# MB_audio_esp.net
KiCad netlist of a schematic drawn in Altium Designer
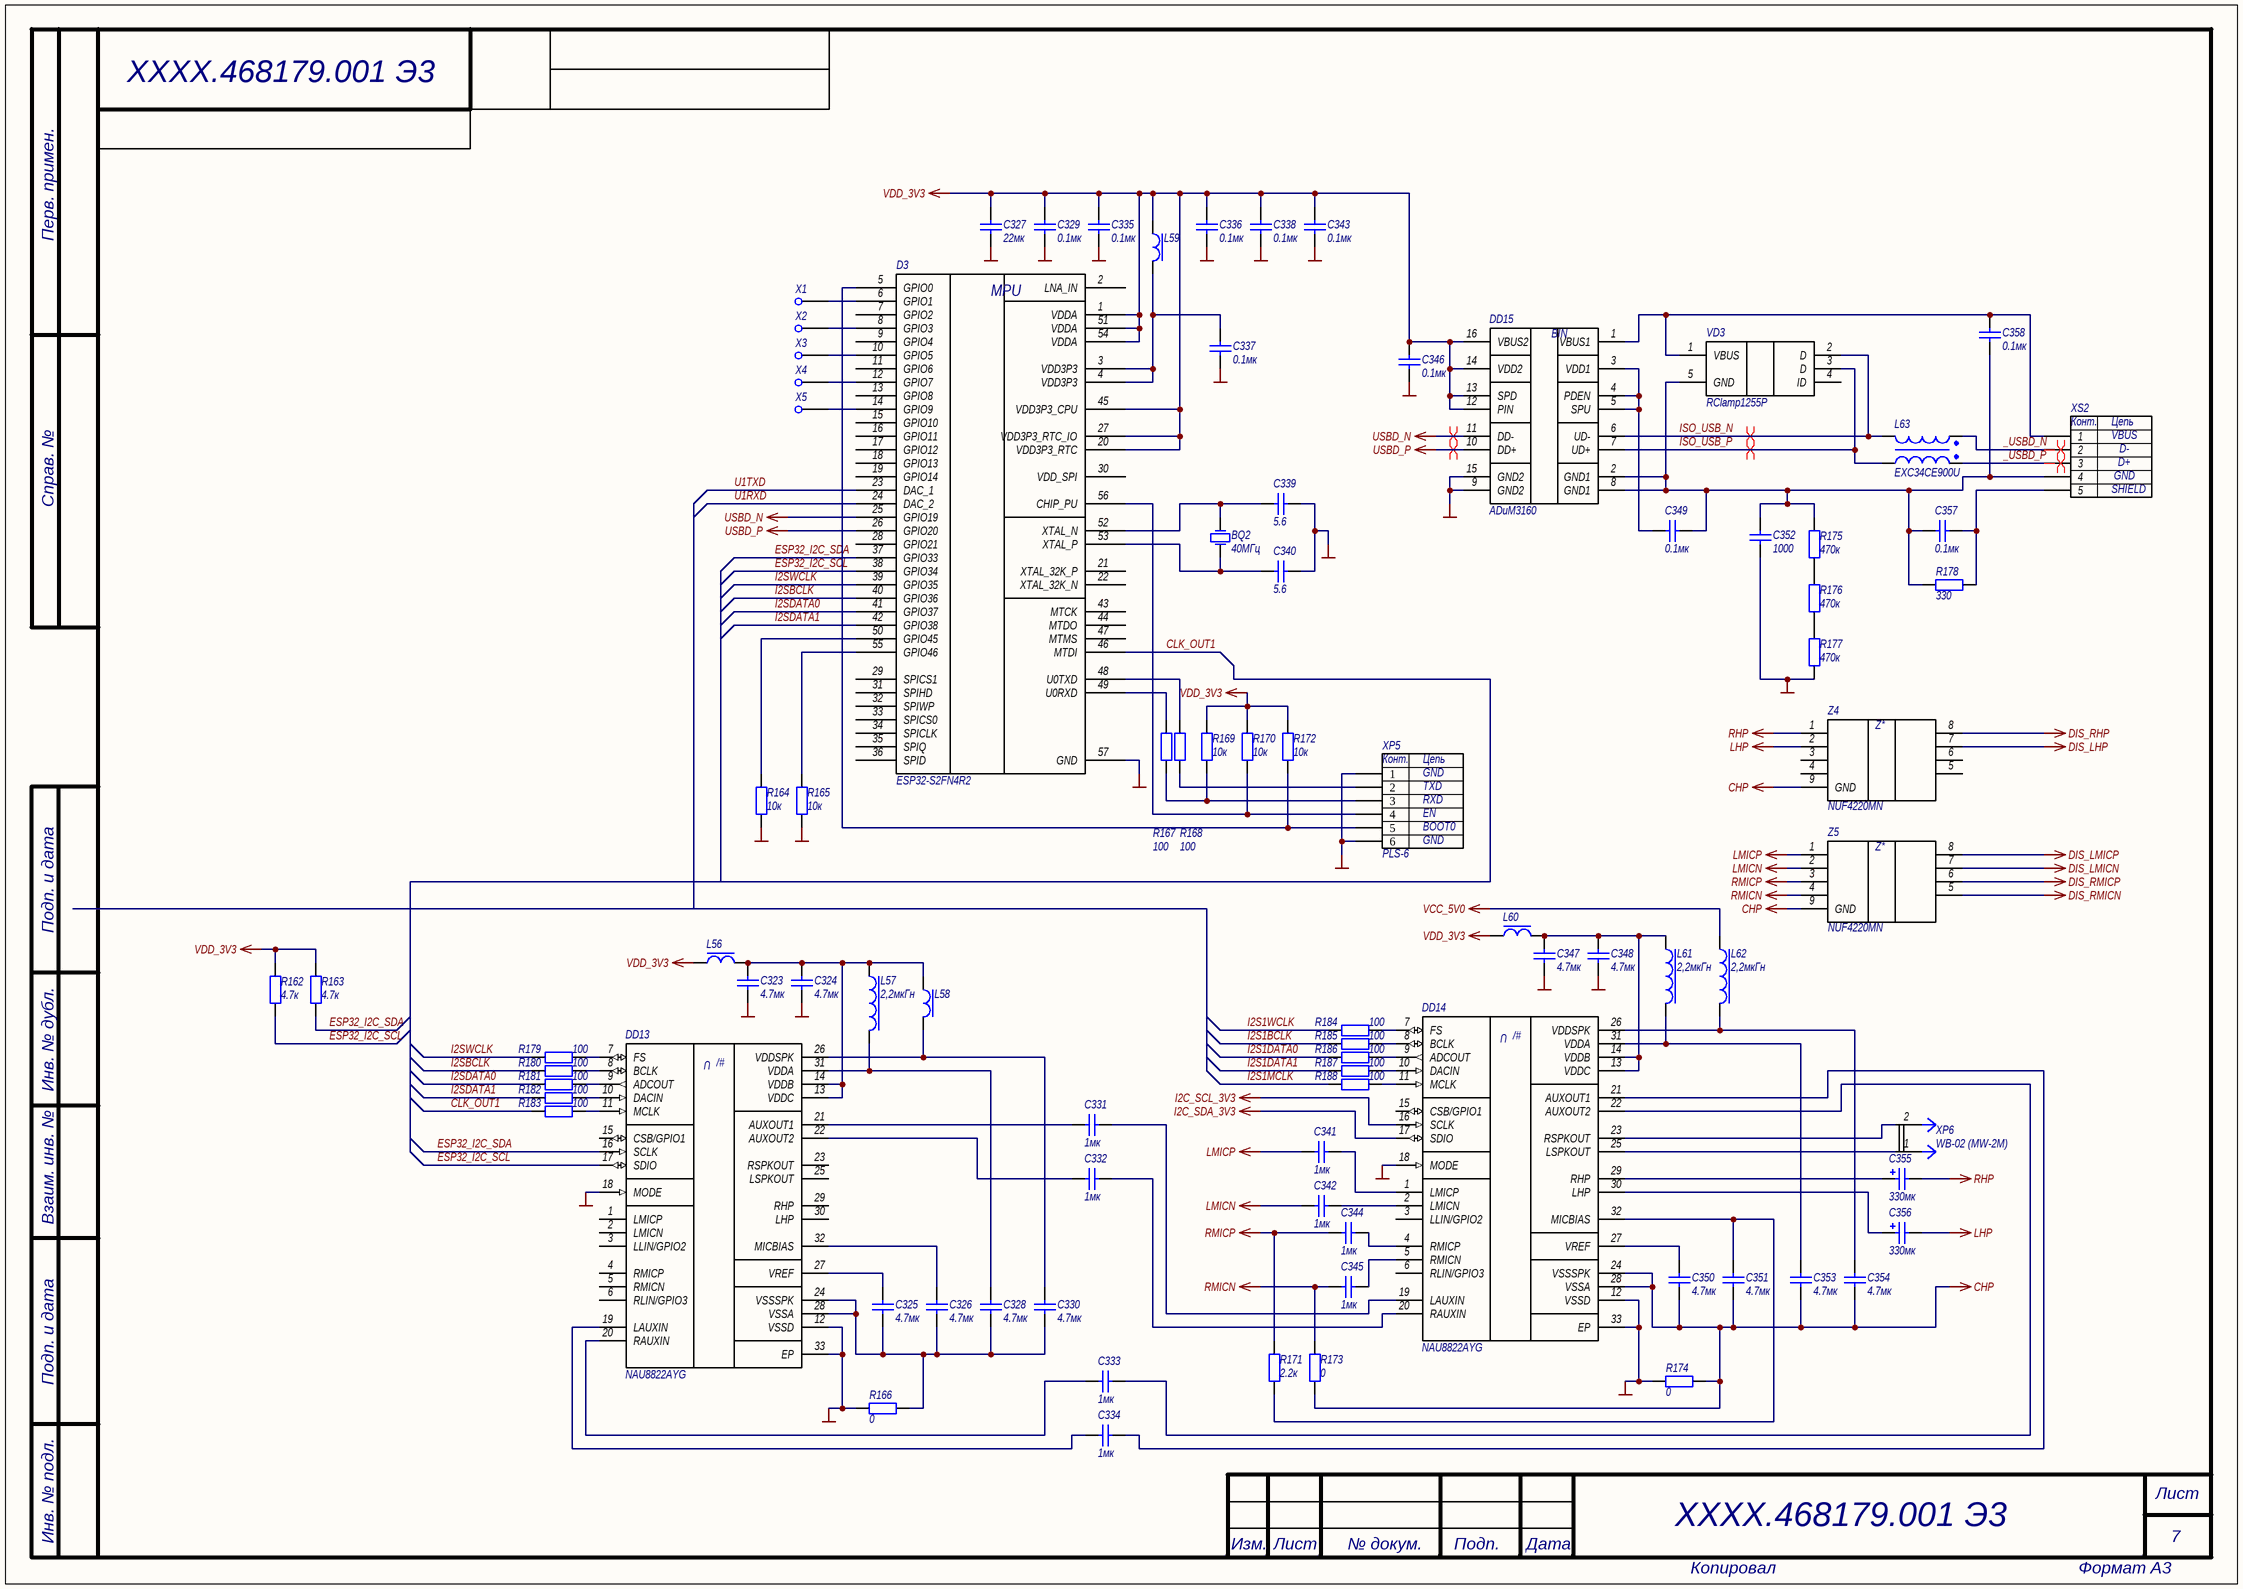
[diagram p0: MB_audio_esp.SchDoc]

(export (version "E")
  (design (tool "Eeschema 10.0.6"))
  (components
    (comp (ref "BQ2")
      (value "40МГц")
      (footprint "ABRACOM ABM10")
      (description "Резонатор кварцевый")
      (fields (field (name "TOLERANCE") "±50 ppm") (field (name "MANUFACTURER") "ABRACON"))
      (libsource (lib "nels_other") (part "Кварц ABM10AIG-40.000MHZ"))
    )
    (comp (ref "C323")
      (value "4.7мк")
      (footprint "CAPC2012X12L")
      (description "Кер. ЧИП-конденсатор")
      (fields (field (name "TOLERANCE") "±20%") (field (name "MANUFACTURER") "Murata"))
      (libsource (lib "nels_caps") (part "Кер.ЧИП конд. 0805 4,7мкФ X5R 20% 16В"))
    )
    (comp (ref "C324")
      (value "4.7мк")
      (footprint "CAPC2012X12L")
      (description "Кер. ЧИП-конденсатор")
      (fields (field (name "TOLERANCE") "±20%") (field (name "MANUFACTURER") "Murata"))
      (libsource (lib "nels_caps") (part "Кер.ЧИП конд. 0805 4,7мкФ X5R 20% 16В"))
    )
    (comp (ref "C325")
      (value "4.7мк")
      (footprint "CAPC2012X12L")
      (description "Кер. ЧИП-конденсатор")
      (fields (field (name "TOLERANCE") "±20%") (field (name "MANUFACTURER") "Murata"))
      (libsource (lib "nels_caps") (part "Кер.ЧИП конд. 0805 4,7мкФ X5R 20% 16В"))
    )
    (comp (ref "C326")
      (value "4.7мк")
      (footprint "CAPC2012X12L")
      (description "Кер. ЧИП-конденсатор")
      (fields (field (name "TOLERANCE") "±20%") (field (name "MANUFACTURER") "Murata"))
      (libsource (lib "nels_caps") (part "Кер.ЧИП конд. 0805 4,7мкФ X5R 20% 16В"))
    )
    (comp (ref "C327")
      (value "22мк")
      (footprint "CAPC2012X12L")
      (description "Кер. ЧИП-конденсатор")
      (fields (field (name "MANUFACTURER") "TDK") (field (name "TOLERANCE") "±10%"))
      (libsource (lib "nels_caps") (part "Кер.ЧИП конд. 0805 22мкФ X5R 10% 16В"))
    )
    (comp (ref "C328")
      (value "4.7мк")
      (footprint "CAPC2012X12L")
      (description "Кер. ЧИП-конденсатор")
      (fields (field (name "TOLERANCE") "±20%") (field (name "MANUFACTURER") "Murata"))
      (libsource (lib "nels_caps") (part "Кер.ЧИП конд. 0805 4,7мкФ X5R 20% 16В"))
    )
    (comp (ref "C329")
      (value "0.1мк")
      (footprint "CAPC1005X06N")
      (description "Кер. ЧИП-конденсатор")
      (fields (field (name "TOLERANCE") "±10%"))
      (libsource (lib "nels") (part "Кер.ЧИП конд. 0402 0.1мкФ X7R 10%, 16В"))
    )
    (comp (ref "C330")
      (value "4.7мк")
      (footprint "CAPC2012X12L")
      (description "Кер. ЧИП-конденсатор")
      (fields (field (name "TOLERANCE") "±20%") (field (name "MANUFACTURER") "Murata"))
      (libsource (lib "nels_caps") (part "Кер.ЧИП конд. 0805 4,7мкФ X5R 20% 16В"))
    )
    (comp (ref "C331")
      (value "1мк")
      (footprint "CAPC1005X06N")
      (description "Кер. ЧИП-конденсатор")
      (fields (field (name "TOLERANCE") "±10%"))
      (libsource (lib "nels_caps") (part "Кер.ЧИП конд. 0402 1мкФ X5R 10%, 10В"))
    )
    (comp (ref "C332")
      (value "1мк")
      (footprint "CAPC1005X06N")
      (description "Кер. ЧИП-конденсатор")
      (fields (field (name "TOLERANCE") "±10%"))
      (libsource (lib "nels_caps") (part "Кер.ЧИП конд. 0402 1мкФ X5R 10%, 10В"))
    )
    (comp (ref "C333")
      (value "1мк")
      (footprint "CAPC1005X06N")
      (description "Кер. ЧИП-конденсатор")
      (fields (field (name "TOLERANCE") "±10%"))
      (libsource (lib "nels_caps") (part "Кер.ЧИП конд. 0402 1мкФ X5R 10%, 10В"))
    )
    (comp (ref "C334")
      (value "1мк")
      (footprint "CAPC1005X06N")
      (description "Кер. ЧИП-конденсатор")
      (fields (field (name "TOLERANCE") "±10%"))
      (libsource (lib "nels_caps") (part "Кер.ЧИП конд. 0402 1мкФ X5R 10%, 10В"))
    )
    (comp (ref "C335")
      (value "0.1мк")
      (footprint "CAPC1005X06N")
      (description "Кер. ЧИП-конденсатор")
      (fields (field (name "TOLERANCE") "±10%"))
      (libsource (lib "nels") (part "Кер.ЧИП конд. 0402 0.1мкФ X7R 10%, 16В"))
    )
    (comp (ref "C336")
      (value "0.1мк")
      (footprint "CAPC1005X06N")
      (description "Кер. ЧИП-конденсатор")
      (fields (field (name "TOLERANCE") "±10%"))
      (libsource (lib "nels") (part "Кер.ЧИП конд. 0402 0.1мкФ X7R 10%, 16В"))
    )
    (comp (ref "C337")
      (value "0.1мк")
      (footprint "CAPC1005X06N")
      (description "Кер. ЧИП-конденсатор")
      (fields (field (name "TOLERANCE") "±10%"))
      (libsource (lib "nels") (part "Кер.ЧИП конд. 0402 0.1мкФ X7R 10%, 16В"))
    )
    (comp (ref "C338")
      (value "0.1мк")
      (footprint "CAPC1005X06N")
      (description "Кер. ЧИП-конденсатор")
      (fields (field (name "TOLERANCE") "±10%"))
      (libsource (lib "nels") (part "Кер.ЧИП конд. 0402 0.1мкФ X7R 10%, 16В"))
    )
    (comp (ref "C339")
      (value "5.6")
      (footprint "CAPC1005X06N")
      (description "Кер. ЧИП-конденсатор")
      (fields (field (name "TOLERANCE") "±5%"))
      (libsource (lib "nels_caps") (part "Кер.ЧИП конд. 0402 5.6пФ C0G, 50В"))
    )
    (comp (ref "C340")
      (value "5.6")
      (footprint "CAPC1005X06N")
      (description "Кер. ЧИП-конденсатор")
      (fields (field (name "TOLERANCE") "±5%"))
      (libsource (lib "nels_caps") (part "Кер.ЧИП конд. 0402 5.6пФ C0G, 50В"))
    )
    (comp (ref "C341")
      (value "1мк")
      (footprint "CAPC1005X06N")
      (description "Кер. ЧИП-конденсатор")
      (fields (field (name "TOLERANCE") "±10%"))
      (libsource (lib "nels_caps") (part "Кер.ЧИП конд. 0402 1мкФ X5R 10%, 10В"))
    )
    (comp (ref "C342")
      (value "1мк")
      (footprint "CAPC1005X06N")
      (description "Кер. ЧИП-конденсатор")
      (fields (field (name "TOLERANCE") "±10%"))
      (libsource (lib "nels_caps") (part "Кер.ЧИП конд. 0402 1мкФ X5R 10%, 10В"))
    )
    (comp (ref "C343")
      (value "0.1мк")
      (footprint "CAPC1005X06N")
      (description "Кер. ЧИП-конденсатор")
      (fields (field (name "TOLERANCE") "±10%"))
      (libsource (lib "nels") (part "Кер.ЧИП конд. 0402 0.1мкФ X7R 10%, 16В"))
    )
    (comp (ref "C344")
      (value "1мк")
      (footprint "CAPC1005X06N")
      (description "Кер. ЧИП-конденсатор")
      (fields (field (name "TOLERANCE") "±10%"))
      (libsource (lib "nels_caps") (part "Кер.ЧИП конд. 0402 1мкФ X5R 10%, 10В"))
    )
    (comp (ref "C345")
      (value "1мк")
      (footprint "CAPC1005X06N")
      (description "Кер. ЧИП-конденсатор")
      (fields (field (name "TOLERANCE") "±10%"))
      (libsource (lib "nels_caps") (part "Кер.ЧИП конд. 0402 1мкФ X5R 10%, 10В"))
    )
    (comp (ref "C346")
      (value "0.1мк")
      (footprint "CAPC1005X06N")
      (description "Кер. ЧИП-конденсатор")
      (fields (field (name "TOLERANCE") "±10%"))
      (libsource (lib "nels") (part "Кер.ЧИП конд. 0402 0.1мкФ X7R 10%, 16В"))
    )
    (comp (ref "C347")
      (value "4.7мк")
      (footprint "CAPC2012X12L")
      (description "Кер. ЧИП-конденсатор")
      (fields (field (name "TOLERANCE") "±20%") (field (name "MANUFACTURER") "Murata"))
      (libsource (lib "nels_caps") (part "Кер.ЧИП конд. 0805 4,7мкФ X5R 20% 16В"))
    )
    (comp (ref "C348")
      (value "4.7мк")
      (footprint "CAPC2012X12L")
      (description "Кер. ЧИП-конденсатор")
      (fields (field (name "TOLERANCE") "±20%") (field (name "MANUFACTURER") "Murata"))
      (libsource (lib "nels_caps") (part "Кер.ЧИП конд. 0805 4,7мкФ X5R 20% 16В"))
    )
    (comp (ref "C349")
      (value "0.1мк")
      (footprint "CAPC1608X08L")
      (description "Кер. ЧИП-конденсатор")
      (fields (field (name "TOLERANCE") "±10%") (field (name "MANUFACTURER") "Murata"))
      (libsource (lib "nels_caps") (part "Кер.ЧИП конд. 0603 0.1мкФ X7R 10% 50В"))
    )
    (comp (ref "C350")
      (value "4.7мк")
      (footprint "CAPC2012X12L")
      (description "Кер. ЧИП-конденсатор")
      (fields (field (name "TOLERANCE") "±20%") (field (name "MANUFACTURER") "Murata"))
      (libsource (lib "nels_caps") (part "Кер.ЧИП конд. 0805 4,7мкФ X5R 20% 16В"))
    )
    (comp (ref "C351")
      (value "4.7мк")
      (footprint "CAPC2012X12L")
      (description "Кер. ЧИП-конденсатор")
      (fields (field (name "TOLERANCE") "±20%") (field (name "MANUFACTURER") "Murata"))
      (libsource (lib "nels_caps") (part "Кер.ЧИП конд. 0805 4,7мкФ X5R 20% 16В"))
    )
    (comp (ref "C352")
      (value "1000")
      (footprint "CAPRD7.5-9x5")
      (description "Защищенные конденсаторы 1000pF 250Vrms 20% L/S=10mm Bulk long")
      (fields
        (field (name "MANUFACTURER") "MURATA")
        (field (name "TOLERANCE") "±10%")
        (field (name "PUBLISHER") "Altium Limited")
      )
      (libsource (lib "nels_caps") (part "Конденсатор керамический защищенный 1000pF 250V AC (DE1E3KX102MA4BN01F)"))
    )
    (comp (ref "C353")
      (value "4.7мк")
      (footprint "CAPC2012X12L")
      (description "Кер. ЧИП-конденсатор")
      (fields (field (name "TOLERANCE") "±20%") (field (name "MANUFACTURER") "Murata"))
      (libsource (lib "nels_caps") (part "Кер.ЧИП конд. 0805 4,7мкФ X5R 20% 16В"))
    )
    (comp (ref "C354")
      (value "4.7мк")
      (footprint "CAPC2012X12L")
      (description "Кер. ЧИП-конденсатор")
      (fields (field (name "TOLERANCE") "±20%") (field (name "MANUFACTURER") "Murata"))
      (libsource (lib "nels_caps") (part "Кер.ЧИП конд. 0805 4,7мкФ X5R 20% 16В"))
    )
    (comp (ref "C355")
      (value "330мк")
      (footprint "CAPAE116103X105N")
      (description "Гибридный ЧИП-конденсатор")
      (fields
        (field (name "TOLERANCE") "±20%")
        (field (name "MANUFACTURER") "Panasonic")
        (field (name "PUBLISHER") "Altium Limited")
      )
      (libsource (lib "nels_caps") (part "Конденсатор гибридный SMD 330мкФ ±20% 35В"))
    )
    (comp (ref "C356")
      (value "330мк")
      (footprint "CAPAE116103X105N")
      (description "Гибридный ЧИП-конденсатор")
      (fields
        (field (name "TOLERANCE") "±20%")
        (field (name "MANUFACTURER") "Panasonic")
        (field (name "PUBLISHER") "Altium Limited")
      )
      (libsource (lib "nels_caps") (part "Конденсатор гибридный SMD 330мкФ ±20% 35В"))
    )
    (comp (ref "C357")
      (value "0.1мк")
      (footprint "CAPC1608X08L")
      (description "Кер. ЧИП-конденсатор")
      (fields (field (name "TOLERANCE") "±10%") (field (name "MANUFACTURER") "Murata"))
      (libsource (lib "nels_caps") (part "Кер.ЧИП конд. 0603 0.1мкФ X7R 10% 50В"))
    )
    (comp (ref "C358")
      (value "0.1мк")
      (footprint "CAPC1608X08L")
      (description "Кер. ЧИП-конденсатор")
      (fields (field (name "TOLERANCE") "±10%") (field (name "MANUFACTURER") "Murata"))
      (libsource (lib "nels_caps") (part "Кер.ЧИП конд. 0603 0.1мкФ X7R 10% 50В"))
    )
    (comp (ref "D3")
      (value "ESP32-S2FN4R2")
      (footprint "QFN40P700X700X80-56N")
      (description "SoC with Xtensa® Single-Core 32-bit LX7 Microprocessor")
      (fields (field (name "MANUFACTURER") "STMicroelectronics") (field (name "PUBLISHER") "Altium Limited"))
      (libsource (lib "nels_chip") (part "Микросхема ESP32-S2FN4R2"))
    )
    (comp (ref "DD13")
      (value "NAU8822AYG")
      (footprint "QFN50P500X500X100_HS-33L")
      (description "24-bit Stereo Audio Codec with Speaker Driver")
      (fields (field (name "MANUFACTURER") "NUVOTON"))
      (libsource (lib "nels_chip") (part "Микросхема NAU8822AYG"))
    )
    (comp (ref "DD14")
      (value "NAU8822AYG")
      (footprint "QFN50P500X500X100_HS-33L")
      (description "24-bit Stereo Audio Codec with Speaker Driver")
      (fields (field (name "MANUFACTURER") "NUVOTON"))
      (libsource (lib "nels_chip") (part "Микросхема NAU8822AYG"))
    )
    (comp (ref "DD15")
      (value "ADuM3160")
      (footprint "SOIC127P1030X265-16N")
      (description "Full/Low Speed 2.5 kV USB Digital Isolator")
      (fields (field (name "MANUFACTURER") "AD"))
      (libsource (lib "nels_chip") (part "Микросхема ADuM3160"))
    )
    (comp (ref "L56")
      (value "BLM18PG121SN1D")
      (footprint "INDC1608X08L")
      (description "SMD EMI Suppression Filter EMIFIL")
      (fields (field (name "MANUFACTURER") "Murata"))
      (libsource (lib "nels_ind") (part "ЧИП дроссель 0603 BLM18PG121SN1D"))
    )
    (comp (ref "L57")
      (value "2,2мкГн")
      (footprint "CSAB0420")
      (description "Molding Power Choke")
      (fields
        (field (name "MANUFACTURER") "Vishay")
        (field (name "MANUFACTURERPARTNUMBER") "IHLP1616ABER1R0M11")
      )
      (libsource (lib "nels_ind") (part "ЧИП индуктивность CSAB0420-2R2M"))
    )
    (comp (ref "L58")
      (value "BLM18PG121SN1D")
      (footprint "INDC1608X08L")
      (description "SMD EMI Suppression Filter EMIFIL")
      (fields (field (name "MANUFACTURER") "Murata"))
      (libsource (lib "nels_ind") (part "ЧИП дроссель 0603 BLM18PG121SN1D"))
    )
    (comp (ref "L59")
      (value "BLM18PG121SN1D")
      (footprint "INDC1608X08L")
      (description "SMD EMI Suppression Filter EMIFIL")
      (fields (field (name "MANUFACTURER") "Murata"))
      (libsource (lib "nels_ind") (part "ЧИП дроссель 0603 BLM18PG121SN1D"))
    )
    (comp (ref "L60")
      (value "BLM18PG121SN1D")
      (footprint "INDC1608X08L")
      (description "SMD EMI Suppression Filter EMIFIL")
      (fields (field (name "MANUFACTURER") "Murata"))
      (libsource (lib "nels_ind") (part "ЧИП дроссель 0603 BLM18PG121SN1D"))
    )
    (comp (ref "L61")
      (value "2,2мкГн")
      (footprint "CSAB0420")
      (description "Molding Power Choke")
      (fields
        (field (name "MANUFACTURER") "Vishay")
        (field (name "MANUFACTURERPARTNUMBER") "IHLP1616ABER1R0M11")
      )
      (libsource (lib "nels_ind") (part "ЧИП индуктивность CSAB0420-2R2M"))
    )
    (comp (ref "L62")
      (value "2,2мкГн")
      (footprint "CSAB0420")
      (description "Molding Power Choke")
      (fields
        (field (name "MANUFACTURER") "Vishay")
        (field (name "MANUFACTURERPARTNUMBER") "IHLP1616ABER1R0M11")
      )
      (libsource (lib "nels_ind") (part "ЧИП индуктивность CSAB0420-2R2M"))
    )
    (comp (ref "L63")
      (value "EXC34CE900U")
      (footprint "EXC34CE900U")
      (description "Common Mode Noise Filters EXC34CG/CE type")
      (fields (field (name "MANUFACTURER") "Panasonic"))
      (libsource (lib "nels_ind") (part "ЧИП синфазный фильтр 0805 EXC34CE900U"))
    )
    (comp (ref "R162")
      (value "4.7к")
      (footprint "RESC1005X06N")
      (description "ЧИП-резистор")
      (fields (field (name "TOLERANCE") "±5%"))
      (libsource (lib "nels_res") (part "Чип резистор 0402 4,7 кОм, 5%"))
    )
    (comp (ref "R163")
      (value "4.7к")
      (footprint "RESC1005X06N")
      (description "ЧИП-резистор")
      (fields (field (name "TOLERANCE") "±5%"))
      (libsource (lib "nels_res") (part "Чип резистор 0402 4,7 кОм, 5%"))
    )
    (comp (ref "R164")
      (value "10к")
      (footprint "RESC1005X06N")
      (description "ЧИП-резистор")
      (fields (field (name "TOLERANCE") "±5%"))
      (libsource (lib "nels_res") (part "Чип резистор 0402 10 кОм, 5%"))
    )
    (comp (ref "R165")
      (value "10к")
      (footprint "RESC1005X06N")
      (description "ЧИП-резистор")
      (fields (field (name "TOLERANCE") "±5%"))
      (libsource (lib "nels_res") (part "Чип резистор 0402 10 кОм, 5%"))
    )
    (comp (ref "R166")
      (value "0")
      (footprint "RESC1005X06N")
      (description "ЧИП-резистор")
      (fields (field (name "TOLERANCE") "±5%"))
      (libsource (lib "") (part "Чип резистор 0402 0 Ом_1"))
    )
    (comp (ref "R167")
      (value "100")
      (footprint "RESC1005X06N")
      (description "ЧИП-резистор")
      (fields (field (name "TOLERANCE") "±5%"))
      (libsource (lib "") (part "Чип резистор 0402 100 Ом, 5%_1"))
    )
    (comp (ref "R168")
      (value "100")
      (footprint "RESC1005X06N")
      (description "ЧИП-резистор")
      (fields (field (name "TOLERANCE") "±5%"))
      (libsource (lib "") (part "Чип резистор 0402 100 Ом, 5%_2"))
    )
    (comp (ref "R169")
      (value "10к")
      (footprint "RESC1005X06N")
      (description "ЧИП-резистор")
      (fields (field (name "TOLERANCE") "±5%"))
      (libsource (lib "nels_res") (part "Чип резистор 0402 10 кОм, 5%"))
    )
    (comp (ref "R170")
      (value "10к")
      (footprint "RESC1005X06N")
      (description "ЧИП-резистор")
      (fields (field (name "TOLERANCE") "±5%"))
      (libsource (lib "nels_res") (part "Чип резистор 0402 10 кОм, 5%"))
    )
    (comp (ref "R171")
      (value "2.2к")
      (footprint "RESC1005X06N")
      (description "ЧИП-резистор")
      (fields (field (name "TOLERANCE") "±5%"))
      (libsource (lib "nels_res") (part "Чип резистор 0402 2,2 кОм, 5%"))
    )
    (comp (ref "R172")
      (value "10к")
      (footprint "RESC1005X06N")
      (description "ЧИП-резистор")
      (fields (field (name "TOLERANCE") "±5%"))
      (libsource (lib "nels_res") (part "Чип резистор 0402 10 кОм, 5%"))
    )
    (comp (ref "R173")
      (value "0")
      (footprint "RESC1005X06N")
      (description "ЧИП-резистор")
      (fields (field (name "TOLERANCE") "±5%"))
      (libsource (lib "nels_res") (part "Чип резистор 0402 0 Ом"))
    )
    (comp (ref "R174")
      (value "0")
      (footprint "RESC1005X06N")
      (description "ЧИП-резистор")
      (fields (field (name "TOLERANCE") "±5%"))
      (libsource (lib "") (part "Чип резистор 0402 0 Ом_1"))
    )
    (comp (ref "R175")
      (value "470к")
      (footprint "RESC1005X06N")
      (description "ЧИП-резистор")
      (fields (field (name "TOLERANCE") "±5%"))
      (libsource (lib "nels_res") (part "Чип резистор 0402 470 кОм, 5%"))
    )
    (comp (ref "R176")
      (value "470к")
      (footprint "RESC1005X06N")
      (description "ЧИП-резистор")
      (fields (field (name "TOLERANCE") "±5%"))
      (libsource (lib "nels_res") (part "Чип резистор 0402 470 кОм, 5%"))
    )
    (comp (ref "R177")
      (value "470к")
      (footprint "RESC1005X06N")
      (description "ЧИП-резистор")
      (fields (field (name "TOLERANCE") "±5%"))
      (libsource (lib "nels_res") (part "Чип резистор 0402 470 кОм, 5%"))
    )
    (comp (ref "R178")
      (value "330")
      (footprint "RESC1005X06N")
      (description "ЧИП-резистор")
      (fields (field (name "TOLERANCE") "±5%"))
      (libsource (lib "nels_res") (part "Чип резистор 0402 330 Ом, 5%"))
    )
    (comp (ref "R179")
      (value "100")
      (footprint "RESC1005X06N")
      (description "ЧИП-резистор")
      (fields (field (name "TOLERANCE") "±5%"))
      (libsource (lib "nels_res") (part "Чип резистор 0402 100 Ом, 5%"))
    )
    (comp (ref "R180")
      (value "100")
      (footprint "RESC1005X06N")
      (description "ЧИП-резистор")
      (fields (field (name "TOLERANCE") "±5%"))
      (libsource (lib "nels_res") (part "Чип резистор 0402 100 Ом, 5%"))
    )
    (comp (ref "R181")
      (value "100")
      (footprint "RESC1005X06N")
      (description "ЧИП-резистор")
      (fields (field (name "TOLERANCE") "±5%"))
      (libsource (lib "nels_res") (part "Чип резистор 0402 100 Ом, 5%"))
    )
    (comp (ref "R182")
      (value "100")
      (footprint "RESC1005X06N")
      (description "ЧИП-резистор")
      (fields (field (name "TOLERANCE") "±5%"))
      (libsource (lib "nels_res") (part "Чип резистор 0402 100 Ом, 5%"))
    )
    (comp (ref "R183")
      (value "100")
      (footprint "RESC1005X06N")
      (description "ЧИП-резистор")
      (fields (field (name "TOLERANCE") "±5%"))
      (libsource (lib "nels_res") (part "Чип резистор 0402 100 Ом, 5%"))
    )
    (comp (ref "R184")
      (value "100")
      (footprint "RESC1005X06N")
      (description "ЧИП-резистор")
      (fields (field (name "TOLERANCE") "±5%"))
      (libsource (lib "nels_res") (part "Чип резистор 0402 100 Ом, 5%"))
    )
    (comp (ref "R185")
      (value "100")
      (footprint "RESC1005X06N")
      (description "ЧИП-резистор")
      (fields (field (name "TOLERANCE") "±5%"))
      (libsource (lib "nels_res") (part "Чип резистор 0402 100 Ом, 5%"))
    )
    (comp (ref "R186")
      (value "100")
      (footprint "RESC1005X06N")
      (description "ЧИП-резистор")
      (fields (field (name "TOLERANCE") "±5%"))
      (libsource (lib "nels_res") (part "Чип резистор 0402 100 Ом, 5%"))
    )
    (comp (ref "R187")
      (value "100")
      (footprint "RESC1005X06N")
      (description "ЧИП-резистор")
      (fields (field (name "TOLERANCE") "±5%"))
      (libsource (lib "nels_res") (part "Чип резистор 0402 100 Ом, 5%"))
    )
    (comp (ref "R188")
      (value "100")
      (footprint "RESC1005X06N")
      (description "ЧИП-резистор")
      (fields (field (name "TOLERANCE") "±5%"))
      (libsource (lib "nels_res") (part "Чип резистор 0402 100 Ом, 5%"))
    )
    (comp (ref "VD3")
      (value "RClamp1255P")
      (footprint "SLP2018P6")
      (description "Low Capacitance RClamp Surge Protection for uUSB Interfaces")
      (fields (field (name "MANUFACTURER") "SEMTECH"))
      (libsource (lib "nels_other") (part "Диодная сборка RClamp1255P"))
    )
    (comp (ref "X1")
      (value "Конструктивный элемент")
      (footprint "PIN2_PROBE")
      (description "Соединитель")
      (libsource (lib "nels_conn") (part "Соединение под пайку"))
    )
    (comp (ref "X2")
      (value "Конструктивный элемент")
      (footprint "PIN2_PROBE")
      (description "Соединитель")
      (libsource (lib "nels_conn") (part "Соединение под пайку"))
    )
    (comp (ref "X3")
      (value "Конструктивный элемент")
      (footprint "PIN2_PROBE")
      (description "Соединитель")
      (libsource (lib "nels_conn") (part "Соединение под пайку"))
    )
    (comp (ref "X4")
      (value "Конструктивный элемент")
      (footprint "PIN2_PROBE")
      (description "Соединитель")
      (libsource (lib "nels_conn") (part "Соединение под пайку"))
    )
    (comp (ref "X5")
      (value "Конструктивный элемент")
      (footprint "PIN2_PROBE")
      (description "Соединитель")
      (libsource (lib "nels_conn") (part "Соединение под пайку"))
    )
    (comp (ref "XP5")
      (value "PLS-6")
      (footprint "HDR1X6")
      (description "Вилка штыревая 2.54мм 1x6 прямая тип1")
      (fields (field (name "PUBLISHER") "Altium Limited"))
      (libsource (lib "nels_conn") (part "Соединитель PLS-6"))
    )
    (comp (ref "XP6")
      (value "WB-02 (MW-2M)")
      (footprint "WB-02 (MW-2M) pitch 2.00mm")
      (description "Соединитель")
      (libsource (lib "nels_conn") (part "Соединитель WB-02 (MW-2M)"))
    )
    (comp (ref "XS2")
      (value "USBB-1J")
      (footprint "USB2.5-2H4D")
      (description "Universal Serial Bus (USB) Shielded I/O Receptacle, Right Angle, Type B")
      (fields (field (name "MANUFACTURER") "Connfly"))
      (libsource (lib "nels_conn") (part "Соединитель USBB-1J"))
    )
    (comp (ref "Z4")
      (value "NUF4220MN")
      (footprint "QFN50P200X200X80_HS-9L")
      (description "ESD/EMI Protection  for Audio Interfaces")
      (fields (field (name "MANUFACTURER") "onsemi"))
      (libsource (lib "nels_other") (part "Фильтр EMI NUF4220MN"))
    )
    (comp (ref "Z5")
      (value "NUF4220MN")
      (footprint "QFN50P200X200X80_HS-9L")
      (description "ESD/EMI Protection  for Audio Interfaces")
      (fields (field (name "MANUFACTURER") "onsemi"))
      (libsource (lib "nels_other") (part "Фильтр EMI NUF4220MN"))
    )
  )
  (nets
    (net (code "1") (name "/CLK_OUT1") (class "Default")
      (node (ref "D3") (pin "46") (pinfunction "MTDI_46") (pintype "passive"))
      (node (ref "R183") (pin "1") (pinfunction "1_1") (pintype "passive"))
    )
    (net (code "2") (name "/ESP32_I2C_SCL") (class "Default")
      (node (ref "D3") (pin "38") (pinfunction "GPIO34_38") (pintype "passive"))
      (node (ref "DD13") (pin "17") (pinfunction "SDIO_17") (pintype "bidirectional"))
      (node (ref "R162") (pin "2") (pinfunction "2_2") (pintype "passive"))
    )
    (net (code "3") (name "/ESP32_I2C_SDA") (class "Default")
      (node (ref "D3") (pin "37") (pinfunction "GPIO33_37") (pintype "passive"))
      (node (ref "DD13") (pin "16") (pinfunction "SCLK_16") (pintype "input"))
      (node (ref "R163") (pin "2") (pinfunction "2_2") (pintype "passive"))
    )
    (net (code "4") (name "/I2S1BCLK") (class "Default")
      (node (ref "R185") (pin "1") (pinfunction "1_1") (pintype "passive"))
    )
    (net (code "5") (name "/I2S1DATA0") (class "Default")
      (node (ref "R186") (pin "1") (pinfunction "1_1") (pintype "passive"))
    )
    (net (code "6") (name "/I2S1DATA1") (class "Default")
      (node (ref "R187") (pin "1") (pinfunction "1_1") (pintype "passive"))
    )
    (net (code "7") (name "/I2S1MCLK") (class "Default")
      (node (ref "R188") (pin "1") (pinfunction "1_1") (pintype "passive"))
    )
    (net (code "8") (name "/I2S1WCLK") (class "Default")
      (node (ref "R184") (pin "1") (pinfunction "1_1") (pintype "passive"))
    )
    (net (code "9") (name "/I2SBCLK") (class "Default")
      (node (ref "D3") (pin "40") (pinfunction "GPIO36_40") (pintype "passive"))
      (node (ref "R180") (pin "1") (pinfunction "1_1") (pintype "passive"))
    )
    (net (code "10") (name "/I2SDATA0") (class "Default")
      (node (ref "D3") (pin "41") (pinfunction "GPIO37_41") (pintype "passive"))
      (node (ref "R181") (pin "1") (pinfunction "1_1") (pintype "passive"))
    )
    (net (code "11") (name "/I2SDATA1") (class "Default")
      (node (ref "D3") (pin "42") (pinfunction "GPIO38_42") (pintype "passive"))
      (node (ref "R182") (pin "1") (pinfunction "1_1") (pintype "passive"))
    )
    (net (code "12") (name "/I2SWCLK") (class "Default")
      (node (ref "D3") (pin "39") (pinfunction "GPIO35_39") (pintype "passive"))
      (node (ref "R179") (pin "1") (pinfunction "1_1") (pintype "passive"))
    )
    (net (code "13") (name "/ISO_USB_N") (class "Default")
      (node (ref "DD15") (pin "6") (pinfunction "UD-_6") (pintype "passive"))
      (node (ref "L63") (pin "2") (pinfunction "2_2") (pintype "passive"))
      (node (ref "VD3") (pin "2") (pinfunction "D_2") (pintype "passive"))
    )
    (net (code "14") (name "/ISO_USB_P") (class "Default")
      (node (ref "DD15") (pin "7") (pinfunction "UD+_7") (pintype "passive"))
      (node (ref "L63") (pin "3") (pinfunction "3_3") (pintype "passive"))
      (node (ref "VD3") (pin "3") (pinfunction "D_3") (pintype "passive"))
    )
    (net (code "15") (name "/U1RXD") (class "Default")
      (node (ref "D3") (pin "24") (pinfunction "DAC_2_24") (pintype "passive"))
    )
    (net (code "16") (name "/U1TXD") (class "Default")
      (node (ref "D3") (pin "23") (pinfunction "DAC_1_23") (pintype "passive"))
    )
    (net (code "17") (name "/_USBD_N") (class "Default")
      (node (ref "L63") (pin "1") (pinfunction "1_1") (pintype "passive"))
      (node (ref "XS2") (pin "2") (pinfunction "2_2") (pintype "passive"))
    )
    (net (code "18") (name "/_USBD_P") (class "Default")
      (node (ref "L63") (pin "4") (pinfunction "4_4") (pintype "passive"))
      (node (ref "XS2") (pin "3") (pinfunction "3_3") (pintype "passive"))
    )
    (net (code "19") (name "CHP") (class "Default")
      (node (ref "C350") (pin "2") (pinfunction "2_2") (pintype "passive"))
      (node (ref "C351") (pin "2") (pinfunction "2_2") (pintype "passive"))
      (node (ref "C353") (pin "2") (pinfunction "2_2") (pintype "passive"))
      (node (ref "C354") (pin "2") (pinfunction "2_2") (pintype "passive"))
      (node (ref "DD14") (pin "24") (pinfunction "VSSSPK_24") (pintype "power_in"))
      (node (ref "DD14") (pin "28") (pinfunction "VSSA_28") (pintype "power_in"))
      (node (ref "R173") (pin "1") (pinfunction "1_1") (pintype "passive"))
      (node (ref "R174") (pin "2") (pinfunction "2_2") (pintype "passive"))
      (node (ref "Z4") (pin "9") (pinfunction "GND_9") (pintype "passive"))
      (node (ref "Z5") (pin "9") (pinfunction "GND_9") (pintype "passive"))
    )
    (net (code "20") (name "DIS_LHP") (class "Default") (node (ref "Z4") (pin "7") (pintype "passive")))
    (net (code "21") (name "DIS_LMICN") (class "Default") (node (ref "Z5") (pin "7") (pintype "passive")))
    (net (code "22") (name "DIS_LMICP") (class "Default") (node (ref "Z5") (pin "8") (pintype "passive")))
    (net (code "23") (name "DIS_RHP") (class "Default") (node (ref "Z4") (pin "8") (pintype "passive")))
    (net (code "24") (name "DIS_RMICN") (class "Default") (node (ref "Z5") (pin "5") (pintype "passive")))
    (net (code "25") (name "DIS_RMICP") (class "Default") (node (ref "Z5") (pin "6") (pintype "passive")))
    (net (code "26") (name "GND") (class "Default")
      (node (ref "C323") (pin "2") (pinfunction "2_2") (pintype "passive"))
      (node (ref "C324") (pin "2") (pinfunction "2_2") (pintype "passive"))
      (node (ref "C327") (pin "1") (pinfunction "1_1") (pintype "passive"))
      (node (ref "C329") (pin "1") (pinfunction "1_1") (pintype "passive"))
      (node (ref "C335") (pin "1") (pinfunction "1_1") (pintype "passive"))
      (node (ref "C336") (pin "1") (pinfunction "1_1") (pintype "passive"))
      (node (ref "C337") (pin "1") (pinfunction "1_1") (pintype "passive"))
      (node (ref "C338") (pin "1") (pinfunction "1_1") (pintype "passive"))
      (node (ref "C339") (pin "1") (pinfunction "1_1") (pintype "passive"))
      (node (ref "C340") (pin "1") (pinfunction "1_1") (pintype "passive"))
      (node (ref "C343") (pin "1") (pinfunction "1_1") (pintype "passive"))
      (node (ref "C346") (pin "1") (pinfunction "1_1") (pintype "passive"))
      (node (ref "C347") (pin "2") (pinfunction "2_2") (pintype "passive"))
      (node (ref "C348") (pin "2") (pinfunction "2_2") (pintype "passive"))
      (node (ref "C352") (pin "2") (pinfunction "2_2") (pintype "passive"))
      (node (ref "D3") (pin "57") (pinfunction "GND_57") (pintype "passive"))
      (node (ref "DD13") (pin "12") (pinfunction "VSSD_12") (pintype "power_in"))
      (node (ref "DD13") (pin "18") (pinfunction "MODE_18") (pintype "input"))
      (node (ref "DD13") (pin "33") (pinfunction "EP_33") (pintype "passive"))
      (node (ref "DD14") (pin "12") (pinfunction "VSSD_12") (pintype "power_in"))
      (node (ref "DD14") (pin "18") (pinfunction "MODE_18") (pintype "input"))
      (node (ref "DD14") (pin "33") (pinfunction "EP_33") (pintype "passive"))
      (node (ref "DD15") (pin "15") (pinfunction "GND2_15") (pintype "passive"))
      (node (ref "DD15") (pin "9") (pinfunction "GND2_9") (pintype "passive"))
      (node (ref "R164") (pin "2") (pinfunction "2_2") (pintype "passive"))
      (node (ref "R165") (pin "2") (pinfunction "2_2") (pintype "passive"))
      (node (ref "R166") (pin "1") (pinfunction "1_1") (pintype "passive"))
      (node (ref "R174") (pin "1") (pinfunction "1_1") (pintype "passive"))
      (node (ref "R177") (pin "1") (pinfunction "1_1") (pintype "passive"))
      (node (ref "XP5") (pin "1") (pinfunction "1_1") (pintype "passive"))
      (node (ref "XP5") (pin "6") (pinfunction "6_6") (pintype "passive"))
    )
    (net (code "27") (name "I2C_SCL_3V3") (class "Default")
      (node (ref "DD14") (pin "16") (pinfunction "SCLK_16") (pintype "input"))
    )
    (net (code "28") (name "I2C_SDA_3V3") (class "Default")
      (node (ref "DD14") (pin "17") (pinfunction "SDIO_17") (pintype "bidirectional"))
    )
    (net (code "29") (name "LHP") (class "Default")
      (node (ref "C356") (pin "2") (pinfunction "2_2") (pintype "passive"))
      (node (ref "Z4") (pin "2") (pintype "passive"))
    )
    (net (code "30") (name "LMICN") (class "Default")
      (node (ref "C342") (pin "1") (pinfunction "1_1") (pintype "passive"))
      (node (ref "Z5") (pin "2") (pintype "passive"))
    )
    (net (code "31") (name "LMICP") (class "Default")
      (node (ref "C341") (pin "1") (pinfunction "1_1") (pintype "passive"))
      (node (ref "Z5") (pin "1") (pintype "passive"))
    )
    (net (code "32") (name "Net-(BQ2-OSC1)") (class "Default")
      (node (ref "BQ2") (pin "1") (pinfunction "OSC1_1") (pintype "passive"))
      (node (ref "C340") (pin "2") (pinfunction "2_2") (pintype "passive"))
      (node (ref "D3") (pin "53") (pinfunction "XTAL_P_53") (pintype "passive"))
    )
    (net (code "33") (name "Net-(BQ2-OSC2)") (class "Default")
      (node (ref "BQ2") (pin "3") (pinfunction "OSC2_3") (pintype "passive"))
      (node (ref "C339") (pin "2") (pinfunction "2_2") (pintype "passive"))
      (node (ref "D3") (pin "52") (pinfunction "XTAL_N_52") (pintype "passive"))
    )
    (net (code "34") (name "Net-(C337-Pad2)") (class "Default")
      (node (ref "C337") (pin "2") (pinfunction "2_2") (pintype "passive"))
      (node (ref "D3") (pin "3") (pinfunction "VDD3P3_3") (pintype "passive"))
      (node (ref "D3") (pin "4") (pinfunction "VDD3P3_4") (pintype "passive"))
      (node (ref "L59") (pin "2") (pinfunction "2_2") (pintype "passive"))
    )
    (net (code "35") (name "Net-(C357-Pad1)") (class "Default")
      (node (ref "C357") (pin "1") (pinfunction "1_1") (pintype "passive"))
      (node (ref "R178") (pin "1") (pinfunction "1_1") (pintype "passive"))
      (node (ref "XS2") (pin "5") (pinfunction "5_5") (pintype "passive"))
    )
    (net (code "36") (name "Net-(D3-CHIP_PU)") (class "Default")
      (node (ref "D3") (pin "56") (pinfunction "CHIP_PU_56") (pintype "passive"))
      (node (ref "R170") (pin "2") (pinfunction "2_2") (pintype "passive"))
      (node (ref "XP5") (pin "4") (pinfunction "4_4") (pintype "passive"))
    )
    (net (code "37") (name "Net-(D3-GPIO0)") (class "Default")
      (node (ref "D3") (pin "5") (pinfunction "GPIO0_5") (pintype "passive"))
      (node (ref "R172") (pin "2") (pinfunction "2_2") (pintype "passive"))
      (node (ref "XP5") (pin "5") (pinfunction "5_5") (pintype "passive"))
    )
    (net (code "38") (name "Net-(D3-GPIO1)") (class "Default")
      (node (ref "D3") (pin "6") (pinfunction "GPIO1_6") (pintype "passive"))
      (node (ref "X1") (pin "1") (pinfunction "~_1") (pintype "passive"))
    )
    (net (code "39") (name "Net-(D3-GPIO3)") (class "Default")
      (node (ref "D3") (pin "8") (pinfunction "GPIO3_8") (pintype "passive"))
      (node (ref "X2") (pin "1") (pinfunction "~_1") (pintype "passive"))
    )
    (net (code "40") (name "Net-(D3-GPIO5)") (class "Default")
      (node (ref "D3") (pin "10") (pinfunction "GPIO5_10") (pintype "passive"))
      (node (ref "X3") (pin "1") (pinfunction "~_1") (pintype "passive"))
    )
    (net (code "41") (name "Net-(D3-GPIO7)") (class "Default")
      (node (ref "D3") (pin "12") (pinfunction "GPIO7_12") (pintype "passive"))
      (node (ref "X4") (pin "1") (pinfunction "~_1") (pintype "passive"))
    )
    (net (code "42") (name "Net-(D3-GPIO9)") (class "Default")
      (node (ref "D3") (pin "14") (pinfunction "GPIO9_14") (pintype "passive"))
      (node (ref "X5") (pin "1") (pinfunction "~_1") (pintype "passive"))
    )
    (net (code "43") (name "Net-(D3-GPIO45)") (class "Default")
      (node (ref "D3") (pin "50") (pinfunction "GPIO45_50") (pintype "passive"))
      (node (ref "R164") (pin "1") (pinfunction "1_1") (pintype "passive"))
    )
    (net (code "44") (name "Net-(D3-GPIO46)") (class "Default")
      (node (ref "D3") (pin "55") (pinfunction "GPIO46_55") (pintype "passive"))
      (node (ref "R165") (pin "1") (pinfunction "1_1") (pintype "passive"))
    )
    (net (code "45") (name "Net-(D3-U0RXD)") (class "Default")
      (node (ref "D3") (pin "49") (pinfunction "U0RXD_49") (pintype "passive"))
      (node (ref "R167") (pin "1") (pinfunction "1_1") (pintype "passive"))
    )
    (net (code "46") (name "Net-(D3-U0TXD)") (class "Default")
      (node (ref "D3") (pin "48") (pinfunction "U0TXD_48") (pintype "passive"))
      (node (ref "R168") (pin "2") (pinfunction "2_2") (pintype "passive"))
    )
    (net (code "47") (name "Net-(DD13-ADCOUT)") (class "Default")
      (node (ref "DD13") (pin "9") (pinfunction "ADCOUT_9") (pintype "output"))
      (node (ref "R181") (pin "2") (pinfunction "2_2") (pintype "passive"))
    )
    (net (code "48") (name "Net-(DD13-AUXOUT1)") (class "Default")
      (node (ref "C331") (pin "1") (pinfunction "1_1") (pintype "passive"))
      (node (ref "DD13") (pin "21") (pinfunction "AUXOUT1_21") (pintype "passive"))
    )
    (net (code "49") (name "Net-(DD13-AUXOUT2)") (class "Default")
      (node (ref "C332") (pin "1") (pinfunction "1_1") (pintype "passive"))
      (node (ref "DD13") (pin "22") (pinfunction "AUXOUT2_22") (pintype "passive"))
    )
    (net (code "50") (name "Net-(DD13-BCLK)") (class "Default")
      (node (ref "DD13") (pin "8") (pinfunction "BCLK_8") (pintype "bidirectional"))
      (node (ref "R180") (pin "2") (pinfunction "2_2") (pintype "passive"))
    )
    (net (code "51") (name "Net-(DD13-DACIN)") (class "Default")
      (node (ref "DD13") (pin "10") (pinfunction "DACIN_10") (pintype "input"))
      (node (ref "R182") (pin "2") (pinfunction "2_2") (pintype "passive"))
    )
    (net (code "52") (name "Net-(DD13-FS)") (class "Default")
      (node (ref "DD13") (pin "7") (pinfunction "FS_7") (pintype "bidirectional"))
      (node (ref "R179") (pin "2") (pinfunction "2_2") (pintype "passive"))
    )
    (net (code "53") (name "Net-(DD13-LAUXIN)") (class "Default")
      (node (ref "C334") (pin "1") (pinfunction "1_1") (pintype "passive"))
      (node (ref "DD13") (pin "19") (pinfunction "LAUXIN_19") (pintype "passive"))
    )
    (net (code "54") (name "Net-(DD13-MCLK)") (class "Default")
      (node (ref "DD13") (pin "11") (pinfunction "MCLK_11") (pintype "input"))
      (node (ref "R183") (pin "2") (pinfunction "2_2") (pintype "passive"))
    )
    (net (code "55") (name "Net-(DD13-MICBIAS)") (class "Default")
      (node (ref "C326") (pin "1") (pinfunction "1_1") (pintype "passive"))
      (node (ref "DD13") (pin "32") (pinfunction "MICBIAS_32") (pintype "passive"))
    )
    (net (code "56") (name "Net-(DD13-RAUXIN)") (class "Default")
      (node (ref "C333") (pin "1") (pinfunction "1_1") (pintype "passive"))
      (node (ref "DD13") (pin "20") (pinfunction "RAUXIN_20") (pintype "passive"))
    )
    (net (code "57") (name "Net-(DD13-VDDA)") (class "Default")
      (node (ref "C328") (pin "1") (pinfunction "1_1") (pintype "passive"))
      (node (ref "DD13") (pin "31") (pinfunction "VDDA_31") (pintype "power_in"))
      (node (ref "L57") (pin "2") (pinfunction "2_2") (pintype "passive"))
    )
    (net (code "58") (name "Net-(DD13-VDDB)") (class "Default")
      (node (ref "C323") (pin "1") (pinfunction "1_1") (pintype "passive"))
      (node (ref "C324") (pin "1") (pinfunction "1_1") (pintype "passive"))
      (node (ref "DD13") (pin "13") (pinfunction "VDDC_13") (pintype "power_in"))
      (node (ref "DD13") (pin "14") (pinfunction "VDDB_14") (pintype "power_in"))
      (node (ref "L56") (pin "2") (pinfunction "2_2") (pintype "passive"))
      (node (ref "L57") (pin "1") (pinfunction "1_1") (pintype "passive"))
      (node (ref "L58") (pin "1") (pinfunction "1_1") (pintype "passive"))
    )
    (net (code "59") (name "Net-(DD13-VDDSPK)") (class "Default")
      (node (ref "C330") (pin "1") (pinfunction "1_1") (pintype "passive"))
      (node (ref "DD13") (pin "26") (pinfunction "VDDSPK_26") (pintype "power_in"))
      (node (ref "L58") (pin "2") (pinfunction "2_2") (pintype "passive"))
    )
    (net (code "60") (name "Net-(DD13-VREF)") (class "Default")
      (node (ref "C325") (pin "1") (pinfunction "1_1") (pintype "passive"))
      (node (ref "DD13") (pin "27") (pinfunction "VREF_27") (pintype "power_in"))
    )
    (net (code "61") (name "Net-(DD13-VSSA)") (class "Default")
      (node (ref "C325") (pin "2") (pinfunction "2_2") (pintype "passive"))
      (node (ref "C326") (pin "2") (pinfunction "2_2") (pintype "passive"))
      (node (ref "C328") (pin "2") (pinfunction "2_2") (pintype "passive"))
      (node (ref "C330") (pin "2") (pinfunction "2_2") (pintype "passive"))
      (node (ref "DD13") (pin "24") (pinfunction "VSSSPK_24") (pintype "power_in"))
      (node (ref "DD13") (pin "28") (pinfunction "VSSA_28") (pintype "power_in"))
      (node (ref "R166") (pin "2") (pinfunction "2_2") (pintype "passive"))
    )
    (net (code "62") (name "Net-(DD14-ADCOUT)") (class "Default")
      (node (ref "DD14") (pin "9") (pinfunction "ADCOUT_9") (pintype "output"))
      (node (ref "R186") (pin "2") (pinfunction "2_2") (pintype "passive"))
    )
    (net (code "63") (name "Net-(DD14-AUXOUT1)") (class "Default")
      (node (ref "C334") (pin "2") (pinfunction "2_2") (pintype "passive"))
      (node (ref "DD14") (pin "21") (pinfunction "AUXOUT1_21") (pintype "passive"))
    )
    (net (code "64") (name "Net-(DD14-AUXOUT2)") (class "Default")
      (node (ref "C333") (pin "2") (pinfunction "2_2") (pintype "passive"))
      (node (ref "DD14") (pin "22") (pinfunction "AUXOUT2_22") (pintype "passive"))
    )
    (net (code "65") (name "Net-(DD14-BCLK)") (class "Default")
      (node (ref "DD14") (pin "8") (pinfunction "BCLK_8") (pintype "bidirectional"))
      (node (ref "R185") (pin "2") (pinfunction "2_2") (pintype "passive"))
    )
    (net (code "66") (name "Net-(DD14-DACIN)") (class "Default")
      (node (ref "DD14") (pin "10") (pinfunction "DACIN_10") (pintype "input"))
      (node (ref "R187") (pin "2") (pinfunction "2_2") (pintype "passive"))
    )
    (net (code "67") (name "Net-(DD14-FS)") (class "Default")
      (node (ref "DD14") (pin "7") (pinfunction "FS_7") (pintype "bidirectional"))
      (node (ref "R184") (pin "2") (pinfunction "2_2") (pintype "passive"))
    )
    (net (code "68") (name "Net-(DD14-LAUXIN)") (class "Default")
      (node (ref "C331") (pin "2") (pinfunction "2_2") (pintype "passive"))
      (node (ref "DD14") (pin "19") (pinfunction "LAUXIN_19") (pintype "passive"))
    )
    (net (code "69") (name "Net-(DD14-LHP)") (class "Default")
      (node (ref "C356") (pin "1") (pinfunction "1_1") (pintype "passive"))
      (node (ref "DD14") (pin "30") (pinfunction "LHP_30") (pintype "passive"))
    )
    (net (code "70") (name "Net-(DD14-LMICN)") (class "Default")
      (node (ref "C342") (pin "2") (pinfunction "2_2") (pintype "passive"))
      (node (ref "DD14") (pin "2") (pinfunction "LMICN_2") (pintype "passive"))
    )
    (net (code "71") (name "Net-(DD14-LMICP)") (class "Default")
      (node (ref "C341") (pin "2") (pinfunction "2_2") (pintype "passive"))
      (node (ref "DD14") (pin "1") (pinfunction "LMICP_1") (pintype "passive"))
    )
    (net (code "72") (name "Net-(DD14-LSPKOUT)") (class "Default")
      (node (ref "DD14") (pin "25") (pinfunction "LSPKOUT_25") (pintype "passive"))
      (node (ref "XP6") (pin "1") (pinfunction "~_1") (pintype "passive"))
    )
    (net (code "73") (name "Net-(DD14-MCLK)") (class "Default")
      (node (ref "DD14") (pin "11") (pinfunction "MCLK_11") (pintype "input"))
      (node (ref "R188") (pin "2") (pinfunction "2_2") (pintype "passive"))
    )
    (net (code "74") (name "Net-(DD14-MICBIAS)") (class "Default")
      (node (ref "C351") (pin "1") (pinfunction "1_1") (pintype "passive"))
      (node (ref "DD14") (pin "32") (pinfunction "MICBIAS_32") (pintype "passive"))
      (node (ref "R171") (pin "1") (pinfunction "1_1") (pintype "passive"))
    )
    (net (code "75") (name "Net-(DD14-RAUXIN)") (class "Default")
      (node (ref "C332") (pin "2") (pinfunction "2_2") (pintype "passive"))
      (node (ref "DD14") (pin "20") (pinfunction "RAUXIN_20") (pintype "passive"))
    )
    (net (code "76") (name "Net-(DD14-RHP)") (class "Default")
      (node (ref "C355") (pin "1") (pinfunction "1_1") (pintype "passive"))
      (node (ref "DD14") (pin "29") (pinfunction "RHP_29") (pintype "passive"))
    )
    (net (code "77") (name "Net-(DD14-RMICN)") (class "Default")
      (node (ref "C345") (pin "2") (pinfunction "2_2") (pintype "passive"))
      (node (ref "DD14") (pin "5") (pinfunction "RMICN_5") (pintype "passive"))
    )
    (net (code "78") (name "Net-(DD14-RMICP)") (class "Default")
      (node (ref "C344") (pin "2") (pinfunction "2_2") (pintype "passive"))
      (node (ref "DD14") (pin "4") (pinfunction "RMICP_4") (pintype "passive"))
    )
    (net (code "79") (name "Net-(DD14-RSPKOUT)") (class "Default")
      (node (ref "DD14") (pin "23") (pinfunction "RSPKOUT_23") (pintype "passive"))
      (node (ref "XP6") (pin "2") (pinfunction "~_2") (pintype "passive"))
    )
    (net (code "80") (name "Net-(DD14-VDDA)") (class "Default")
      (node (ref "C353") (pin "1") (pinfunction "1_1") (pintype "passive"))
      (node (ref "DD14") (pin "31") (pinfunction "VDDA_31") (pintype "power_in"))
      (node (ref "L61") (pin "2") (pinfunction "2_2") (pintype "passive"))
    )
    (net (code "81") (name "Net-(DD14-VDDB)") (class "Default")
      (node (ref "C347") (pin "1") (pinfunction "1_1") (pintype "passive"))
      (node (ref "C348") (pin "1") (pinfunction "1_1") (pintype "passive"))
      (node (ref "DD14") (pin "13") (pinfunction "VDDC_13") (pintype "power_in"))
      (node (ref "DD14") (pin "14") (pinfunction "VDDB_14") (pintype "power_in"))
      (node (ref "L60") (pin "2") (pinfunction "2_2") (pintype "passive"))
      (node (ref "L61") (pin "1") (pinfunction "1_1") (pintype "passive"))
    )
    (net (code "82") (name "Net-(DD14-VDDSPK)") (class "Default")
      (node (ref "C354") (pin "1") (pinfunction "1_1") (pintype "passive"))
      (node (ref "DD14") (pin "26") (pinfunction "VDDSPK_26") (pintype "power_in"))
      (node (ref "L62") (pin "2") (pinfunction "2_2") (pintype "passive"))
    )
    (net (code "83") (name "Net-(DD14-VREF)") (class "Default")
      (node (ref "C350") (pin "1") (pinfunction "1_1") (pintype "passive"))
      (node (ref "DD14") (pin "27") (pinfunction "VREF_27") (pintype "power_in"))
    )
    (net (code "84") (name "Net-(DD15-PDEN)") (class "Default")
      (node (ref "C349") (pin "2") (pinfunction "2_2") (pintype "passive"))
      (node (ref "DD15") (pin "3") (pinfunction "VDD1_3") (pintype "passive"))
      (node (ref "DD15") (pin "4") (pinfunction "PDEN_4") (pintype "passive"))
      (node (ref "DD15") (pin "5") (pinfunction "SPU_5") (pintype "passive"))
    )
    (net (code "85") (name "Net-(DD15-VBUS1)") (class "Default")
      (node (ref "C358") (pin "2") (pinfunction "2_2") (pintype "passive"))
      (node (ref "DD15") (pin "1") (pinfunction "VBUS1_1") (pintype "passive"))
      (node (ref "VD3") (pin "1") (pinfunction "VBUS_1") (pintype "passive"))
      (node (ref "XS2") (pin "1") (pinfunction "1_1") (pintype "passive"))
    )
    (net (code "86") (name "Net-(R167-Pad2)") (class "Default")
      (node (ref "R167") (pin "2") (pinfunction "2_2") (pintype "passive"))
      (node (ref "R169") (pin "2") (pinfunction "2_2") (pintype "passive"))
      (node (ref "XP5") (pin "3") (pinfunction "3_3") (pintype "passive"))
    )
    (net (code "87") (name "Net-(R168-Pad1)") (class "Default")
      (node (ref "R168") (pin "1") (pinfunction "1_1") (pintype "passive"))
      (node (ref "XP5") (pin "2") (pinfunction "2_2") (pintype "passive"))
    )
    (net (code "88") (name "Net-(R175-Pad1)") (class "Default")
      (node (ref "R175") (pin "1") (pinfunction "1_1") (pintype "passive"))
      (node (ref "R176") (pin "2") (pinfunction "2_2") (pintype "passive"))
    )
    (net (code "89") (name "Net-(R176-Pad1)") (class "Default")
      (node (ref "R176") (pin "1") (pinfunction "1_1") (pintype "passive"))
      (node (ref "R177") (pin "2") (pinfunction "2_2") (pintype "passive"))
    )
    (net (code "90") (name "Net-(VD3-GND)") (class "Default")
      (node (ref "C349") (pin "1") (pinfunction "1_1") (pintype "passive"))
      (node (ref "C352") (pin "1") (pinfunction "1_1") (pintype "passive"))
      (node (ref "C357") (pin "2") (pinfunction "2_2") (pintype "passive"))
      (node (ref "C358") (pin "1") (pinfunction "1_1") (pintype "passive"))
      (node (ref "DD15") (pin "2") (pinfunction "GND1_2") (pintype "passive"))
      (node (ref "DD15") (pin "8") (pinfunction "GND1_8") (pintype "passive"))
      (node (ref "R175") (pin "2") (pinfunction "2_2") (pintype "passive"))
      (node (ref "R178") (pin "2") (pinfunction "2_2") (pintype "passive"))
      (node (ref "VD3") (pin "5") (pinfunction "GND_5") (pintype "passive"))
      (node (ref "XS2") (pin "4") (pinfunction "4_4") (pintype "passive"))
    )
    (net (code "91") (name "RHP") (class "Default")
      (node (ref "C355") (pin "2") (pinfunction "2_2") (pintype "passive"))
      (node (ref "Z4") (pin "1") (pintype "passive"))
    )
    (net (code "92") (name "RMICN") (class "Default")
      (node (ref "C345") (pin "1") (pinfunction "1_1") (pintype "passive"))
      (node (ref "R173") (pin "2") (pinfunction "2_2") (pintype "passive"))
      (node (ref "Z5") (pin "4") (pintype "passive"))
    )
    (net (code "93") (name "RMICP") (class "Default")
      (node (ref "C344") (pin "1") (pinfunction "1_1") (pintype "passive"))
      (node (ref "R171") (pin "2") (pinfunction "2_2") (pintype "passive"))
      (node (ref "Z5") (pin "3") (pintype "passive"))
    )
    (net (code "94") (name "USBD_N") (class "Default")
      (node (ref "D3") (pin "25") (pinfunction "GPIO19_25") (pintype "passive"))
      (node (ref "DD15") (pin "11") (pinfunction "DD-_11") (pintype "passive"))
    )
    (net (code "95") (name "USBD_P") (class "Default")
      (node (ref "D3") (pin "26") (pinfunction "GPIO20_26") (pintype "passive"))
      (node (ref "DD15") (pin "10") (pinfunction "DD+_10") (pintype "passive"))
    )
    (net (code "96") (name "VCC_5V0") (class "Default")
      (node (ref "L62") (pin "1") (pinfunction "1_1") (pintype "passive"))
    )
    (net (code "97") (name "VDD_3V3") (class "Default")
      (node (ref "C327") (pin "2") (pinfunction "2_2") (pintype "passive"))
      (node (ref "C329") (pin "2") (pinfunction "2_2") (pintype "passive"))
      (node (ref "C335") (pin "2") (pinfunction "2_2") (pintype "passive"))
      (node (ref "C336") (pin "2") (pinfunction "2_2") (pintype "passive"))
      (node (ref "C338") (pin "2") (pinfunction "2_2") (pintype "passive"))
      (node (ref "C343") (pin "2") (pinfunction "2_2") (pintype "passive"))
      (node (ref "C346") (pin "2") (pinfunction "2_2") (pintype "passive"))
      (node (ref "D3") (pin "1") (pinfunction "VDDA_1") (pintype "passive"))
      (node (ref "D3") (pin "20") (pinfunction "VDD3P3_RTC_20") (pintype "passive"))
      (node (ref "D3") (pin "27") (pinfunction "VDD3P3_RTC_IO_27") (pintype "passive"))
      (node (ref "D3") (pin "45") (pinfunction "VDD3P3_CPU_45") (pintype "passive"))
      (node (ref "D3") (pin "51") (pinfunction "VDDA_51") (pintype "passive"))
      (node (ref "D3") (pin "54") (pinfunction "VDDA_54") (pintype "passive"))
      (node (ref "DD15") (pin "12") (pinfunction "PIN_12") (pintype "passive"))
      (node (ref "DD15") (pin "13") (pinfunction "SPD_13") (pintype "passive"))
      (node (ref "DD15") (pin "14") (pinfunction "VDD2_14") (pintype "passive"))
      (node (ref "DD15") (pin "16") (pinfunction "VBUS2_16") (pintype "passive"))
      (node (ref "L56") (pin "1") (pinfunction "1_1") (pintype "passive"))
      (node (ref "L59") (pin "1") (pinfunction "1_1") (pintype "passive"))
      (node (ref "L60") (pin "1") (pinfunction "1_1") (pintype "passive"))
      (node (ref "R162") (pin "1") (pinfunction "1_1") (pintype "passive"))
      (node (ref "R163") (pin "1") (pinfunction "1_1") (pintype "passive"))
      (node (ref "R169") (pin "1") (pinfunction "1_1") (pintype "passive"))
      (node (ref "R170") (pin "1") (pinfunction "1_1") (pintype "passive"))
      (node (ref "R172") (pin "1") (pinfunction "1_1") (pintype "passive"))
    )
    (net (code "98") (name "unconnected-(D3-GPIO2-Pad7)") (class "Default")
      (node (ref "D3") (pin "7") (pinfunction "GPIO2_7") (pintype "passive"))
    )
    (net (code "99") (name "unconnected-(D3-GPIO4-Pad9)") (class "Default")
      (node (ref "D3") (pin "9") (pinfunction "GPIO4_9") (pintype "passive"))
    )
    (net (code "100") (name "unconnected-(D3-GPIO6-Pad11)") (class "Default")
      (node (ref "D3") (pin "11") (pinfunction "GPIO6_11") (pintype "passive"))
    )
    (net (code "101") (name "unconnected-(D3-GPIO8-Pad13)") (class "Default")
      (node (ref "D3") (pin "13") (pinfunction "GPIO8_13") (pintype "passive"))
    )
    (net (code "102") (name "unconnected-(D3-GPIO10-Pad15)") (class "Default")
      (node (ref "D3") (pin "15") (pinfunction "GPIO10_15") (pintype "passive"))
    )
    (net (code "103") (name "unconnected-(D3-GPIO11-Pad16)") (class "Default")
      (node (ref "D3") (pin "16") (pinfunction "GPIO11_16") (pintype "passive"))
    )
    (net (code "104") (name "unconnected-(D3-GPIO12-Pad17)") (class "Default")
      (node (ref "D3") (pin "17") (pinfunction "GPIO12_17") (pintype "passive"))
    )
    (net (code "105") (name "unconnected-(D3-GPIO13-Pad18)") (class "Default")
      (node (ref "D3") (pin "18") (pinfunction "GPIO13_18") (pintype "passive"))
    )
    (net (code "106") (name "unconnected-(D3-GPIO14-Pad19)") (class "Default")
      (node (ref "D3") (pin "19") (pinfunction "GPIO14_19") (pintype "passive"))
    )
    (net (code "107") (name "unconnected-(D3-GPIO21-Pad28)") (class "Default")
      (node (ref "D3") (pin "28") (pinfunction "GPIO21_28") (pintype "passive"))
    )
    (net (code "108") (name "unconnected-(D3-LNA_IN-Pad2)") (class "Default")
      (node (ref "D3") (pin "2") (pinfunction "LNA_IN_2") (pintype "passive"))
    )
    (net (code "109") (name "unconnected-(D3-MTCK-Pad43)") (class "Default")
      (node (ref "D3") (pin "43") (pinfunction "MTCK_43") (pintype "passive"))
    )
    (net (code "110") (name "unconnected-(D3-MTDO-Pad44)") (class "Default")
      (node (ref "D3") (pin "44") (pinfunction "MTDO_44") (pintype "passive"))
    )
    (net (code "111") (name "unconnected-(D3-MTMS-Pad47)") (class "Default")
      (node (ref "D3") (pin "47") (pinfunction "MTMS_47") (pintype "passive"))
    )
    (net (code "112") (name "unconnected-(D3-SPICLK-Pad34)") (class "Default")
      (node (ref "D3") (pin "34") (pinfunction "SPICLK_34") (pintype "passive"))
    )
    (net (code "113") (name "unconnected-(D3-SPICS0-Pad33)") (class "Default")
      (node (ref "D3") (pin "33") (pinfunction "SPICS0_33") (pintype "passive"))
    )
    (net (code "114") (name "unconnected-(D3-SPICS1-Pad29)") (class "Default")
      (node (ref "D3") (pin "29") (pinfunction "SPICS1_29") (pintype "passive"))
    )
    (net (code "115") (name "unconnected-(D3-SPID-Pad36)") (class "Default")
      (node (ref "D3") (pin "36") (pinfunction "SPID_36") (pintype "passive"))
    )
    (net (code "116") (name "unconnected-(D3-SPIHD-Pad31)") (class "Default")
      (node (ref "D3") (pin "31") (pinfunction "SPIHD_31") (pintype "passive"))
    )
    (net (code "117") (name "unconnected-(D3-SPIQ-Pad35)") (class "Default")
      (node (ref "D3") (pin "35") (pinfunction "SPIQ_35") (pintype "passive"))
    )
    (net (code "118") (name "unconnected-(D3-SPIWP-Pad32)") (class "Default")
      (node (ref "D3") (pin "32") (pinfunction "SPIWP_32") (pintype "passive"))
    )
    (net (code "119") (name "unconnected-(D3-VDD_SPI-Pad30)") (class "Default")
      (node (ref "D3") (pin "30") (pinfunction "VDD_SPI_30") (pintype "passive"))
    )
    (net (code "120") (name "unconnected-(D3-XTAL_32K_N-Pad22)") (class "Default")
      (node (ref "D3") (pin "22") (pinfunction "XTAL_32K_N_22") (pintype "passive"))
    )
    (net (code "121") (name "unconnected-(D3-XTAL_32K_P-Pad21)") (class "Default")
      (node (ref "D3") (pin "21") (pinfunction "XTAL_32K_P_21") (pintype "passive"))
    )
    (net (code "122") (name "unconnected-(DD13-CSB{slash}GPIO1-Pad15)") (class "Default")
      (node (ref "DD13") (pin "15") (pinfunction "CSB/GPIO1_15") (pintype "bidirectional"))
    )
    (net (code "123") (name "unconnected-(DD13-LHP-Pad30)") (class "Default")
      (node (ref "DD13") (pin "30") (pinfunction "LHP_30") (pintype "passive"))
    )
    (net (code "124") (name "unconnected-(DD13-LLIN{slash}GPIO2-Pad3)") (class "Default")
      (node (ref "DD13") (pin "3") (pinfunction "LLIN/GPIO2_3") (pintype "passive"))
    )
    (net (code "125") (name "unconnected-(DD13-LMICN-Pad2)") (class "Default")
      (node (ref "DD13") (pin "2") (pinfunction "LMICN_2") (pintype "passive"))
    )
    (net (code "126") (name "unconnected-(DD13-LMICP-Pad1)") (class "Default")
      (node (ref "DD13") (pin "1") (pinfunction "LMICP_1") (pintype "passive"))
    )
    (net (code "127") (name "unconnected-(DD13-LSPKOUT-Pad25)") (class "Default")
      (node (ref "DD13") (pin "25") (pinfunction "LSPKOUT_25") (pintype "passive"))
    )
    (net (code "128") (name "unconnected-(DD13-RHP-Pad29)") (class "Default")
      (node (ref "DD13") (pin "29") (pinfunction "RHP_29") (pintype "passive"))
    )
    (net (code "129") (name "unconnected-(DD13-RLIN{slash}GPIO3-Pad6)") (class "Default")
      (node (ref "DD13") (pin "6") (pinfunction "RLIN/GPIO3_6") (pintype "passive"))
    )
    (net (code "130") (name "unconnected-(DD13-RMICN-Pad5)") (class "Default")
      (node (ref "DD13") (pin "5") (pinfunction "RMICN_5") (pintype "passive"))
    )
    (net (code "131") (name "unconnected-(DD13-RMICP-Pad4)") (class "Default")
      (node (ref "DD13") (pin "4") (pinfunction "RMICP_4") (pintype "passive"))
    )
    (net (code "132") (name "unconnected-(DD13-RSPKOUT-Pad23)") (class "Default")
      (node (ref "DD13") (pin "23") (pinfunction "RSPKOUT_23") (pintype "passive"))
    )
    (net (code "133") (name "unconnected-(DD14-CSB{slash}GPIO1-Pad15)") (class "Default")
      (node (ref "DD14") (pin "15") (pinfunction "CSB/GPIO1_15") (pintype "bidirectional"))
    )
    (net (code "134") (name "unconnected-(DD14-LLIN{slash}GPIO2-Pad3)") (class "Default")
      (node (ref "DD14") (pin "3") (pinfunction "LLIN/GPIO2_3") (pintype "passive"))
    )
    (net (code "135") (name "unconnected-(DD14-RLIN{slash}GPIO3-Pad6)") (class "Default")
      (node (ref "DD14") (pin "6") (pinfunction "RLIN/GPIO3_6") (pintype "passive"))
    )
    (net (code "136") (name "unconnected-(VD3-ID-Pad4)") (class "Default")
      (node (ref "VD3") (pin "4") (pinfunction "ID_4") (pintype "passive"))
    )
    (net (code "137") (name "unconnected-(Z4-Pad3)") (class "Default")
      (node (ref "Z4") (pin "3") (pintype "passive"))
    )
    (net (code "138") (name "unconnected-(Z4-Pad4)") (class "Default")
      (node (ref "Z4") (pin "4") (pintype "passive"))
    )
    (net (code "139") (name "unconnected-(Z4-Pad5)") (class "Default")
      (node (ref "Z4") (pin "5") (pintype "passive"))
    )
    (net (code "140") (name "unconnected-(Z4-Pad6)") (class "Default")
      (node (ref "Z4") (pin "6") (pintype "passive"))
    )
  )
)
